# DAC4-20mA-ADC-0-10V.net
KiCad netlist of a schematic drawn in Altium Designer
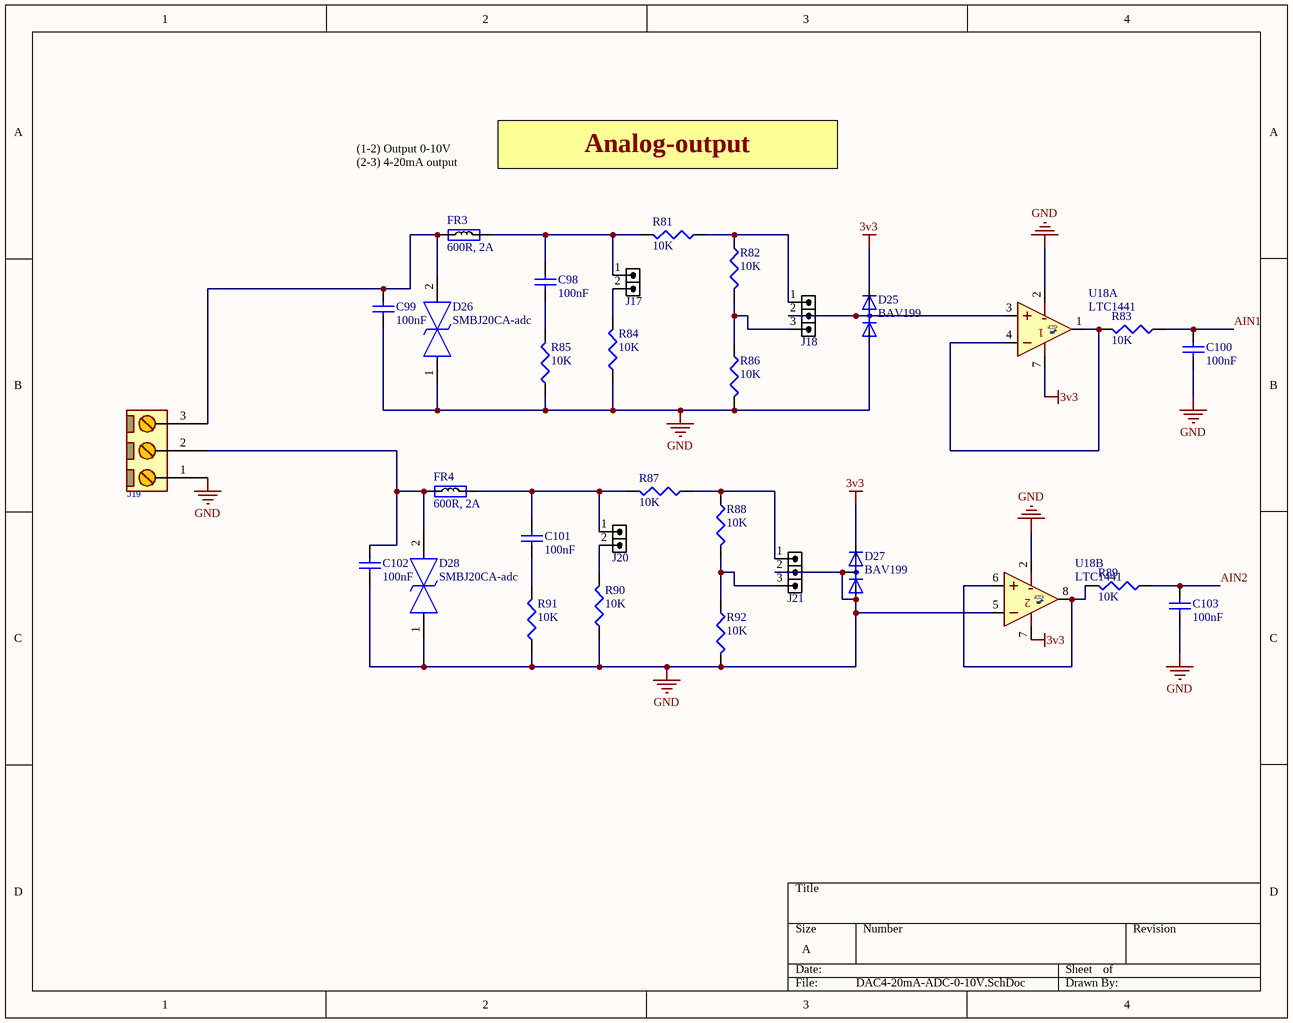
[diagram p0: DAC4-20mA-ADC-0-10V.SchDoc]

(export (version "E")
  (design (tool "Eeschema 10.0.6"))
  (components
    (comp (ref "C98")
      (value "100nF")
      (footprint "c0603")
      (description "0.10µF 50V Ceramic Capacitor X7R 0603")
      (fields
        (field (name "MANUFACTURER PART NUMBER") "CL10B104KB8SFNC")
        (field (name "DIGI-KEY PART NUMBER") "1276-1936-1-ND")
      )
      (libsource (lib "lib-hiony") (part "Cap Semi"))
    )
    (comp (ref "C99")
      (value "100nF")
      (footprint "c0603")
      (description "0.10µF 50V Ceramic Capacitor X7R 0603")
      (fields
        (field (name "MANUFACTURER PART NUMBER") "CL10B104KB8SFNC")
        (field (name "DIGI-KEY PART NUMBER") "1276-1936-1-ND")
      )
      (libsource (lib "lib-hiony") (part "Cap Semi"))
    )
    (comp (ref "C100")
      (value "100nF")
      (footprint "c0603")
      (description "0.10µF 50V Ceramic Capacitor X7R 0603")
      (fields
        (field (name "MANUFACTURER PART NUMBER") "CL10B104KB8SFNC")
        (field (name "DIGI-KEY PART NUMBER") "1276-1936-1-ND")
      )
      (libsource (lib "lib-hiony") (part "Cap Semi"))
    )
    (comp (ref "C101")
      (value "100nF")
      (footprint "c0603")
      (description "0.10µF 50V Ceramic Capacitor X7R 0603")
      (fields
        (field (name "MANUFACTURER PART NUMBER") "CL10B104KB8SFNC")
        (field (name "DIGI-KEY PART NUMBER") "1276-1936-1-ND")
      )
      (libsource (lib "lib-hiony") (part "Cap Semi"))
    )
    (comp (ref "C102")
      (value "100nF")
      (footprint "c0603")
      (description "0.10µF 50V Ceramic Capacitor X7R 0603")
      (fields
        (field (name "MANUFACTURER PART NUMBER") "CL10B104KB8SFNC")
        (field (name "DIGI-KEY PART NUMBER") "1276-1936-1-ND")
      )
      (libsource (lib "lib-hiony") (part "Cap Semi"))
    )
    (comp (ref "C103")
      (value "100nF")
      (footprint "c0603")
      (description "0.10µF 50V Ceramic Capacitor X7R 0603")
      (fields
        (field (name "MANUFACTURER PART NUMBER") "CL10B104KB8SFNC")
        (field (name "DIGI-KEY PART NUMBER") "1276-1936-1-ND")
      )
      (libsource (lib "lib-hiony") (part "Cap Semi"))
    )
    (comp (ref "D25")
      (value "BAV199")
      (footprint "SOT323_3")
      (fields (field (name "MF") "Diodes"))
      (libsource (lib "lib-hiony") (part "BAV199"))
    )
    (comp (ref "D26")
      (value "SMBJ20CA-adc")
      (footprint "ESD_XDFN2")
      (description "TVS Diode (Bi-directional)")
      (fields
        (field (name "MANUFACTURER_PART_NUMBER") "SMBJ20CA")
        (field (name "MOUSER PART NUMBER") "512-SMBJ20CA")
      )
      (libsource (lib "lib-hiony") (part "SMBJ20CA-adc"))
    )
    (comp (ref "D27")
      (value "BAV199")
      (footprint "SOT323_3")
      (fields (field (name "MF") "Diodes"))
      (libsource (lib "lib-hiony") (part "BAV199"))
    )
    (comp (ref "D28")
      (value "SMBJ20CA-adc")
      (footprint "ESD_XDFN2")
      (description "TVS Diode (Bi-directional)")
      (fields
        (field (name "MANUFACTURER_PART_NUMBER") "SMBJ20CA")
        (field (name "MOUSER PART NUMBER") "512-SMBJ20CA")
      )
      (libsource (lib "lib-hiony") (part "SMBJ20CA-adc"))
    )
    (comp (ref "FR3")
      (value "600R, 2A")
      (footprint "RES0805")
      (fields (field (name "MANUFACTURER") "TDK Corporation"))
      (libsource (lib "lib-hiony") (part "Ferrite"))
    )
    (comp (ref "FR4")
      (value "600R, 2A")
      (footprint "RES0805")
      (fields (field (name "MANUFACTURER") "TDK Corporation"))
      (libsource (lib "lib-hiony") (part "Ferrite"))
    )
    (comp (ref "J17")
      (value "HDRM2")
      (footprint "HDR_M_1X2")
      (description "CONN, HEADER, Male, pitch: 2.54mm, 2POS")
      (libsource (lib "conn_header_2.54_st") (part "HDR_M_1X2"))
    )
    (comp (ref "J18")
      (value "HDRM3")
      (footprint "HDR_M_1X3")
      (description "CONN, HEADER, Male, pitch: 2.54mm, 3POS")
      (libsource (lib "conn_header_2.54_st") (part "HDR_M_1X3"))
    )
    (comp (ref "J19")
      (value "CONN_TB3")
      (footprint "MSTB_3")
      (description "CONN, PHOENIX MSTB, 5-G, 5.08mm pitch")
      (libsource (lib "conn_power_terminalB") (part "CONN_MSTB_3"))
    )
    (comp (ref "J20")
      (value "HDRM2")
      (footprint "HDR_M_1X2")
      (description "CONN, HEADER, Male, pitch: 2.54mm, 2POS")
      (libsource (lib "conn_header_2.54_st") (part "HDR_M_1X2"))
    )
    (comp (ref "J21")
      (value "HDRM3")
      (footprint "HDR_M_1X3")
      (description "CONN, HEADER, Male, pitch: 2.54mm, 3POS")
      (libsource (lib "conn_header_2.54_st") (part "HDR_M_1X3"))
    )
    (comp (ref "R81")
      (value "10K")
      (footprint "RES 0603_1608")
      (description "RES SMD 10K OHM 1% 1/10W 0603")
      (fields
        (field (name "DIGI-KEY PART NUMBER") "1276-3485-1-ND")
        (field (name "MANUFACTURER PART NUMBER") "RC1608F103CS")
      )
      (libsource (lib "lib-hiony") (part "Res3_1"))
    )
    (comp (ref "R82")
      (value "10K")
      (footprint "RES 0603_1608")
      (description "RES SMD 10K OHM 1% 1/10W 0603")
      (fields
        (field (name "DIGI-KEY PART NUMBER") "1276-3485-1-ND")
        (field (name "MANUFACTURER PART NUMBER") "RC1608F103CS")
      )
      (libsource (lib "lib-hiony") (part "Res3_1"))
    )
    (comp (ref "R83")
      (value "10K")
      (footprint "RES 0603_1608")
      (description "RES SMD 10K OHM 1% 1/10W 0603")
      (fields
        (field (name "DIGI-KEY PART NUMBER") "1276-3485-1-ND")
        (field (name "MANUFACTURER PART NUMBER") "RC1608F103CS")
      )
      (libsource (lib "lib-hiony") (part "Res3_1"))
    )
    (comp (ref "R84")
      (value "10K")
      (footprint "RES 0603_1608")
      (description "RES SMD 10K OHM 1% 1/10W 0603")
      (fields
        (field (name "DIGI-KEY PART NUMBER") "1276-3485-1-ND")
        (field (name "MANUFACTURER PART NUMBER") "RC1608F103CS")
      )
      (libsource (lib "lib-hiony") (part "Res3_1"))
    )
    (comp (ref "R85")
      (value "10K")
      (footprint "RES 0603_1608")
      (description "RES SMD 10K OHM 1% 1/10W 0603")
      (fields
        (field (name "DIGI-KEY PART NUMBER") "1276-3485-1-ND")
        (field (name "MANUFACTURER PART NUMBER") "RC1608F103CS")
      )
      (libsource (lib "lib-hiony") (part "Res3_1"))
    )
    (comp (ref "R86")
      (value "10K")
      (footprint "RES 0603_1608")
      (description "RES SMD 10K OHM 1% 1/10W 0603")
      (fields
        (field (name "DIGI-KEY PART NUMBER") "1276-3485-1-ND")
        (field (name "MANUFACTURER PART NUMBER") "RC1608F103CS")
      )
      (libsource (lib "lib-hiony") (part "Res3_1"))
    )
    (comp (ref "R87")
      (value "10K")
      (footprint "RES 0603_1608")
      (description "RES SMD 10K OHM 1% 1/10W 0603")
      (fields
        (field (name "DIGI-KEY PART NUMBER") "1276-3485-1-ND")
        (field (name "MANUFACTURER PART NUMBER") "RC1608F103CS")
      )
      (libsource (lib "lib-hiony") (part "Res3_1"))
    )
    (comp (ref "R88")
      (value "10K")
      (footprint "RES 0603_1608")
      (description "RES SMD 10K OHM 1% 1/10W 0603")
      (fields
        (field (name "DIGI-KEY PART NUMBER") "1276-3485-1-ND")
        (field (name "MANUFACTURER PART NUMBER") "RC1608F103CS")
      )
      (libsource (lib "lib-hiony") (part "Res3_1"))
    )
    (comp (ref "R89")
      (value "10K")
      (footprint "RES 0603_1608")
      (description "RES SMD 10K OHM 1% 1/10W 0603")
      (fields
        (field (name "DIGI-KEY PART NUMBER") "1276-3485-1-ND")
        (field (name "MANUFACTURER PART NUMBER") "RC1608F103CS")
      )
      (libsource (lib "lib-hiony") (part "Res3_1"))
    )
    (comp (ref "R90")
      (value "10K")
      (footprint "RES 0603_1608")
      (description "RES SMD 10K OHM 1% 1/10W 0603")
      (fields
        (field (name "DIGI-KEY PART NUMBER") "1276-3485-1-ND")
        (field (name "MANUFACTURER PART NUMBER") "RC1608F103CS")
      )
      (libsource (lib "lib-hiony") (part "Res3_1"))
    )
    (comp (ref "R91")
      (value "10K")
      (footprint "RES 0603_1608")
      (description "RES SMD 10K OHM 1% 1/10W 0603")
      (fields
        (field (name "DIGI-KEY PART NUMBER") "1276-3485-1-ND")
        (field (name "MANUFACTURER PART NUMBER") "RC1608F103CS")
      )
      (libsource (lib "lib-hiony") (part "Res3_1"))
    )
    (comp (ref "R92")
      (value "10K")
      (footprint "RES 0603_1608")
      (description "RES SMD 10K OHM 1% 1/10W 0603")
      (fields
        (field (name "DIGI-KEY PART NUMBER") "1276-3485-1-ND")
        (field (name "MANUFACTURER PART NUMBER") "RC1608F103CS")
      )
      (libsource (lib "lib-hiony") (part "Res3_1"))
    )
    (comp (ref "U18")
      (value "LTC1441")
      (footprint "SO_8")
      (description "Comparator, Dual, Ultralow Power, with Reference")
      (fields (field (name "MANF") "Linear Technology") (field (name "MANF_P#") "LTC1441CS8, LTC1441IS8"))
      (libsource (lib "amp_comparator") (part "LTC1441_SOP8"))
    )
  )
  (nets
    (net (code "1") (name "/AIN1") (class "Default")
      (node (ref "C100") (pin "2") (pinfunction "2_2") (pintype "passive"))
      (node (ref "R83") (pin "1") (pinfunction "1_1") (pintype "passive"))
    )
    (net (code "2") (name "/AIN2") (class "Default")
      (node (ref "C103") (pin "2") (pinfunction "2_2") (pintype "passive"))
      (node (ref "R89") (pin "1") (pinfunction "1_1") (pintype "passive"))
    )
    (net (code "3") (name "3v3") (class "Default")
      (node (ref "D25") (pin "2") (pinfunction "C_2") (pintype "passive"))
      (node (ref "D27") (pin "2") (pinfunction "C_2") (pintype "passive"))
      (node (ref "U18") (pin "7") (pinfunction "V+_7") (pintype "passive"))
    )
    (net (code "4") (name "GND") (class "Default")
      (node (ref "C100") (pin "1") (pinfunction "1_1") (pintype "passive"))
      (node (ref "C102") (pin "1") (pinfunction "1_1") (pintype "passive"))
      (node (ref "C103") (pin "1") (pinfunction "1_1") (pintype "passive"))
      (node (ref "C99") (pin "1") (pinfunction "1_1") (pintype "passive"))
      (node (ref "D25") (pin "1") (pinfunction "A_1") (pintype "passive"))
      (node (ref "D26") (pin "1") (pinfunction "1_1") (pintype "passive"))
      (node (ref "D27") (pin "1") (pinfunction "A_1") (pintype "passive"))
      (node (ref "D27") (pin "3") (pinfunction "AC_3") (pintype "passive"))
      (node (ref "D28") (pin "1") (pinfunction "1_1") (pintype "passive"))
      (node (ref "J19") (pin "1") (pinfunction "1_1") (pintype "passive"))
      (node (ref "J21") (pin "2") (pinfunction "2_2") (pintype "passive"))
      (node (ref "R84") (pin "1") (pinfunction "1_1") (pintype "passive"))
      (node (ref "R85") (pin "1") (pinfunction "1_1") (pintype "passive"))
      (node (ref "R86") (pin "2") (pinfunction "2_2") (pintype "passive"))
      (node (ref "R90") (pin "1") (pinfunction "1_1") (pintype "passive"))
      (node (ref "R91") (pin "1") (pinfunction "1_1") (pintype "passive"))
      (node (ref "R92") (pin "2") (pinfunction "2_2") (pintype "passive"))
      (node (ref "U18") (pin "2") (pinfunction "V-_2") (pintype "passive"))
      (node (ref "U18") (pin "5") (pinfunction "IN-_5") (pintype "passive"))
    )
    (net (code "5") (name "Net-(C98-Pad1)") (class "Default")
      (node (ref "C98") (pin "1") (pinfunction "1_1") (pintype "passive"))
      (node (ref "R85") (pin "2") (pinfunction "2_2") (pintype "passive"))
    )
    (net (code "6") (name "Net-(C98-Pad2)") (class "Default")
      (node (ref "C98") (pin "2") (pinfunction "2_2") (pintype "passive"))
      (node (ref "FR3") (pin "2") (pinfunction "2_2") (pintype "passive"))
      (node (ref "J17") (pin "1") (pinfunction "1_1") (pintype "passive"))
      (node (ref "R81") (pin "2") (pinfunction "2_2") (pintype "passive"))
    )
    (net (code "7") (name "Net-(C99-Pad2)") (class "Default")
      (node (ref "C99") (pin "2") (pinfunction "2_2") (pintype "passive"))
      (node (ref "D26") (pin "2") (pinfunction "2_2") (pintype "passive"))
      (node (ref "FR3") (pin "1") (pinfunction "1_1") (pintype "passive"))
      (node (ref "J19") (pin "3") (pinfunction "3_3") (pintype "passive"))
    )
    (net (code "8") (name "Net-(C101-Pad1)") (class "Default")
      (node (ref "C101") (pin "1") (pinfunction "1_1") (pintype "passive"))
      (node (ref "R91") (pin "2") (pinfunction "2_2") (pintype "passive"))
    )
    (net (code "9") (name "Net-(C101-Pad2)") (class "Default")
      (node (ref "C101") (pin "2") (pinfunction "2_2") (pintype "passive"))
      (node (ref "FR4") (pin "2") (pinfunction "2_2") (pintype "passive"))
      (node (ref "J20") (pin "1") (pinfunction "1_1") (pintype "passive"))
      (node (ref "R87") (pin "2") (pinfunction "2_2") (pintype "passive"))
    )
    (net (code "10") (name "Net-(C102-Pad2)") (class "Default")
      (node (ref "C102") (pin "2") (pinfunction "2_2") (pintype "passive"))
      (node (ref "D28") (pin "2") (pinfunction "2_2") (pintype "passive"))
      (node (ref "FR4") (pin "1") (pinfunction "1_1") (pintype "passive"))
      (node (ref "J19") (pin "2") (pinfunction "2_2") (pintype "passive"))
    )
    (net (code "11") (name "Net-(D25-AC)") (class "Default")
      (node (ref "D25") (pin "3") (pinfunction "AC_3") (pintype "passive"))
      (node (ref "J18") (pin "2") (pinfunction "2_2") (pintype "passive"))
      (node (ref "U18") (pin "3") (pinfunction "IN+_3") (pintype "passive"))
    )
    (net (code "12") (name "Net-(J17-Pad2)") (class "Default")
      (node (ref "J17") (pin "2") (pinfunction "2_2") (pintype "passive"))
      (node (ref "R84") (pin "2") (pinfunction "2_2") (pintype "passive"))
    )
    (net (code "13") (name "Net-(J18-Pad1)") (class "Default")
      (node (ref "J18") (pin "1") (pinfunction "1_1") (pintype "passive"))
      (node (ref "R81") (pin "1") (pinfunction "1_1") (pintype "passive"))
      (node (ref "R82") (pin "1") (pinfunction "1_1") (pintype "passive"))
    )
    (net (code "14") (name "Net-(J18-Pad3)") (class "Default")
      (node (ref "J18") (pin "3") (pinfunction "3_3") (pintype "passive"))
      (node (ref "R82") (pin "2") (pinfunction "2_2") (pintype "passive"))
      (node (ref "R86") (pin "1") (pinfunction "1_1") (pintype "passive"))
    )
    (net (code "15") (name "Net-(J20-Pad2)") (class "Default")
      (node (ref "J20") (pin "2") (pinfunction "2_2") (pintype "passive"))
      (node (ref "R90") (pin "2") (pinfunction "2_2") (pintype "passive"))
    )
    (net (code "16") (name "Net-(J21-Pad1)") (class "Default")
      (node (ref "J21") (pin "1") (pinfunction "1_1") (pintype "passive"))
      (node (ref "R87") (pin "1") (pinfunction "1_1") (pintype "passive"))
      (node (ref "R88") (pin "1") (pinfunction "1_1") (pintype "passive"))
    )
    (net (code "17") (name "Net-(J21-Pad3)") (class "Default")
      (node (ref "J21") (pin "3") (pinfunction "3_3") (pintype "passive"))
      (node (ref "R88") (pin "2") (pinfunction "2_2") (pintype "passive"))
      (node (ref "R92") (pin "1") (pinfunction "1_1") (pintype "passive"))
    )
    (net (code "18") (name "Net-(U18A-IN-)") (class "Default")
      (node (ref "R83") (pin "2") (pinfunction "2_2") (pintype "passive"))
      (node (ref "U18") (pin "1") (pinfunction "OUT_1") (pintype "passive"))
      (node (ref "U18") (pin "4") (pinfunction "IN-_4") (pintype "passive"))
    )
    (net (code "19") (name "Net-(U18B-IN+)") (class "Default")
      (node (ref "R89") (pin "2") (pinfunction "2_2") (pintype "passive"))
      (node (ref "U18") (pin "6") (pinfunction "IN+_6") (pintype "passive"))
      (node (ref "U18") (pin "8") (pinfunction "OUT_8") (pintype "passive"))
    )
  )
)
